# Stepper-driver.net
KiCad netlist of a schematic drawn in Altium Designer
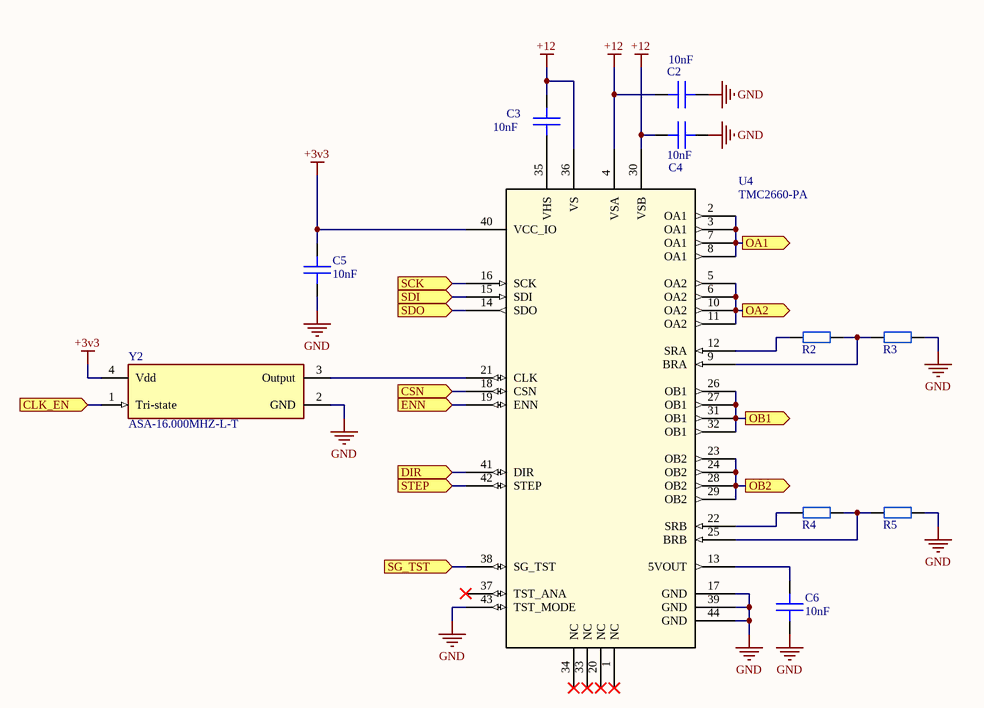
[diagram p0: Stepper-driver.SchDoc]

(export (version "E")
  (design (tool "Eeschema 10.0.6"))
  (components
    (comp (ref "C2")
      (value "10nF")
      (footprint "C0603 (1608)")
      (fields (field (name "Comment") "Cap SMD"))
      (libsource (lib "Moto Symbol Lib") (part "Cap SMD"))
    )
    (comp (ref "C3")
      (value "10nF")
      (footprint "C0603 (1608)")
      (fields (field (name "Comment") "Cap SMD"))
      (libsource (lib "Moto Symbol Lib") (part "Cap SMD"))
    )
    (comp (ref "C4")
      (value "10nF")
      (footprint "C0603 (1608)")
      (fields (field (name "Comment") "Cap SMD"))
      (libsource (lib "Moto Symbol Lib") (part "Cap SMD"))
    )
    (comp (ref "C5")
      (value "10nF")
      (footprint "C0603 (1608)")
      (fields (field (name "Comment") "Cap SMD"))
      (libsource (lib "Moto Symbol Lib") (part "Cap SMD"))
    )
    (comp (ref "C6")
      (value "10nF")
      (footprint "C0603 (1608)")
      (fields (field (name "Comment") "Cap SMD"))
      (libsource (lib "Moto Symbol Lib") (part "Cap SMD"))
    )
    (comp (ref "R2")
      (value "Res")
      (footprint "R0603 (1608)")
      (libsource (lib "Moto Symbol Lib") (part "Resistor EU"))
    )
    (comp (ref "R3")
      (value "Res")
      (footprint "R0603 (1608)")
      (libsource (lib "Moto Symbol Lib") (part "Resistor EU"))
    )
    (comp (ref "R4")
      (value "Res")
      (footprint "R0603 (1608)")
      (libsource (lib "Moto Symbol Lib") (part "Resistor EU"))
    )
    (comp (ref "R5")
      (value "Res")
      (footprint "R0603 (1608)")
      (libsource (lib "Moto Symbol Lib") (part "Resistor EU"))
    )
    (comp (ref "U4")
      (value "TMC2660-PA")
      (footprint "LQFP44_12X12_TRI-M")
      (description "No Description Available")
      (fields (field (name "COPYRIGHT") "Copyright (C) 2016 Accelerated Designs. All rights reserved"))
      (libsource (lib "Moto Symbol Lib") (part "TMC2660-PA"))
    )
    (comp (ref "Y2")
      (value "ASA-16.000MHZ-L-T")
      (footprint "FP-ASA-MFG")
      (description "XTAL OSC XO 16.0000MHZ HCMOS SMD")
      (fields
        (field (name "OCTOPART") "https://octopart.com/asa-16.000mhz-l-t-abracon-21707822")
        (field (name "MANUFACTURER") "Abracon")
      )
      (libsource (lib "Altium Content Vault") (part "7c953fa1d91b086b7cda9813af2bec8"))
    )
  )
  (nets
    (net (code "1") (name "+3v3") (class "Default")
      (node (ref "C5") (pin "2") (pinfunction "2_2") (pintype "power_in"))
      (node (ref "U4") (pin "40") (pinfunction "VCC_IO_40") (pintype "power_in"))
      (node (ref "Y2") (pin "4") (pinfunction "Vdd_4") (pintype "power_in"))
    )
    (net (code "2") (name "+12") (class "Default")
      (node (ref "C2") (pin "2") (pinfunction "2_2") (pintype "power_in"))
      (node (ref "C3") (pin "1") (pinfunction "1_1") (pintype "power_in"))
      (node (ref "C4") (pin "2") (pinfunction "2_2") (pintype "power_in"))
      (node (ref "U4") (pin "30") (pinfunction "VSB_30") (pintype "power_in"))
      (node (ref "U4") (pin "36") (pinfunction "VS_36") (pintype "power_in"))
      (node (ref "U4") (pin "4") (pinfunction "VSA_4") (pintype "power_in"))
    )
    (net (code "3") (name "/CLK_EN") (class "Default")
      (node (ref "Y2") (pin "1") (pinfunction "Tri-state_1") (pintype "input"))
    )
    (net (code "4") (name "/CSN") (class "Default")
      (node (ref "U4") (pin "18") (pinfunction "CSN_18") (pintype "bidirectional"))
    )
    (net (code "5") (name "/DIR") (class "Default")
      (node (ref "U4") (pin "41") (pinfunction "DIR_41") (pintype "bidirectional"))
    )
    (net (code "6") (name "/ENN") (class "Default")
      (node (ref "U4") (pin "19") (pinfunction "ENN_19") (pintype "bidirectional"))
    )
    (net (code "7") (name "/OA1") (class "Default")
      (node (ref "U4") (pin "2") (pinfunction "OA1_2") (pintype "output"))
      (node (ref "U4") (pin "3") (pinfunction "OA1_3") (pintype "output"))
      (node (ref "U4") (pin "7") (pinfunction "OA1_7") (pintype "output"))
      (node (ref "U4") (pin "8") (pinfunction "OA1_8") (pintype "output"))
    )
    (net (code "8") (name "/OA2") (class "Default")
      (node (ref "U4") (pin "10") (pinfunction "OA2_10") (pintype "output"))
      (node (ref "U4") (pin "11") (pinfunction "OA2_11") (pintype "output"))
      (node (ref "U4") (pin "5") (pinfunction "OA2_5") (pintype "output"))
      (node (ref "U4") (pin "6") (pinfunction "OA2_6") (pintype "output"))
    )
    (net (code "9") (name "/OB1") (class "Default")
      (node (ref "U4") (pin "26") (pinfunction "OB1_26") (pintype "output"))
      (node (ref "U4") (pin "27") (pinfunction "OB1_27") (pintype "output"))
      (node (ref "U4") (pin "31") (pinfunction "OB1_31") (pintype "output"))
      (node (ref "U4") (pin "32") (pinfunction "OB1_32") (pintype "output"))
    )
    (net (code "10") (name "/OB2") (class "Default")
      (node (ref "U4") (pin "23") (pinfunction "OB2_23") (pintype "output"))
      (node (ref "U4") (pin "24") (pinfunction "OB2_24") (pintype "output"))
      (node (ref "U4") (pin "28") (pinfunction "OB2_28") (pintype "output"))
      (node (ref "U4") (pin "29") (pinfunction "OB2_29") (pintype "output"))
    )
    (net (code "11") (name "/SCK") (class "Default")
      (node (ref "U4") (pin "16") (pinfunction "SCK_16") (pintype "input"))
    )
    (net (code "12") (name "/SDI") (class "Default")
      (node (ref "U4") (pin "15") (pinfunction "SDI_15") (pintype "input"))
    )
    (net (code "13") (name "/SDO") (class "Default")
      (node (ref "U4") (pin "14") (pinfunction "SDO_14") (pintype "output"))
    )
    (net (code "14") (name "/SG_TST") (class "Default")
      (node (ref "U4") (pin "38") (pinfunction "SG_TST_38") (pintype "bidirectional"))
    )
    (net (code "15") (name "/STEP") (class "Default")
      (node (ref "U4") (pin "42") (pinfunction "STEP_42") (pintype "bidirectional"))
    )
    (net (code "16") (name "GND") (class "Default")
      (node (ref "C2") (pin "1") (pinfunction "1_1") (pintype "power_in"))
      (node (ref "C4") (pin "1") (pinfunction "1_1") (pintype "power_in"))
      (node (ref "C5") (pin "1") (pinfunction "1_1") (pintype "power_in"))
      (node (ref "C6") (pin "1") (pinfunction "1_1") (pintype "power_in"))
      (node (ref "R3") (pin "2") (pinfunction "2_2") (pintype "power_in"))
      (node (ref "R5") (pin "2") (pinfunction "2_2") (pintype "power_in"))
      (node (ref "U4") (pin "17") (pinfunction "GND_17") (pintype "power_in"))
      (node (ref "U4") (pin "39") (pinfunction "GND_39") (pintype "power_in"))
      (node (ref "U4") (pin "43") (pinfunction "TST_MODE_43") (pintype "bidirectional"))
      (node (ref "U4") (pin "44") (pinfunction "GND_44") (pintype "power_in"))
      (node (ref "Y2") (pin "2") (pinfunction "GND_2") (pintype "power_in"))
    )
    (net (code "17") (name "Net-(U4-5VOUT)") (class "Default")
      (node (ref "C6") (pin "2") (pinfunction "2_2") (pintype "power_in"))
      (node (ref "U4") (pin "13") (pinfunction "5VOUT_13") (pintype "output"))
    )
    (net (code "18") (name "Net-(U4-BRA)") (class "Default")
      (node (ref "R2") (pin "2") (pinfunction "2_2") (pintype "power_in"))
      (node (ref "R3") (pin "1") (pinfunction "1_1") (pintype "power_in"))
      (node (ref "U4") (pin "9") (pinfunction "BRA_9") (pintype "input"))
    )
    (net (code "19") (name "Net-(U4-BRB)") (class "Default")
      (node (ref "R4") (pin "2") (pinfunction "2_2") (pintype "power_in"))
      (node (ref "R5") (pin "1") (pinfunction "1_1") (pintype "power_in"))
      (node (ref "U4") (pin "25") (pinfunction "BRB_25") (pintype "input"))
    )
    (net (code "20") (name "Net-(U4-CLK)") (class "Default")
      (node (ref "U4") (pin "21") (pinfunction "CLK_21") (pintype "bidirectional"))
      (node (ref "Y2") (pin "3") (pinfunction "Output_3") (pintype "passive"))
    )
    (net (code "21") (name "Net-(U4-SRA)") (class "Default")
      (node (ref "R2") (pin "1") (pinfunction "1_1") (pintype "power_in"))
      (node (ref "U4") (pin "12") (pinfunction "SRA_12") (pintype "input"))
    )
    (net (code "22") (name "Net-(U4-SRB)") (class "Default")
      (node (ref "R4") (pin "1") (pinfunction "1_1") (pintype "power_in"))
      (node (ref "U4") (pin "22") (pinfunction "SRB_22") (pintype "input"))
    )
    (net (code "23") (name "Net-(U4-VHS)") (class "Default")
      (node (ref "C3") (pin "2") (pinfunction "2_2") (pintype "power_in"))
      (node (ref "U4") (pin "35") (pinfunction "VHS_35") (pintype "power_in"))
    )
    (net (code "24") (name "unconnected-(U4-NC-Pad1)") (class "Default")
      (node (ref "U4") (pin "1") (pinfunction "NC_1") (pintype "passive+no_connect"))
    )
    (net (code "25") (name "unconnected-(U4-NC-Pad20)") (class "Default")
      (node (ref "U4") (pin "20") (pinfunction "NC_20") (pintype "passive+no_connect"))
    )
    (net (code "26") (name "unconnected-(U4-NC-Pad33)") (class "Default")
      (node (ref "U4") (pin "33") (pinfunction "NC_33") (pintype "passive+no_connect"))
    )
    (net (code "27") (name "unconnected-(U4-NC-Pad34)") (class "Default")
      (node (ref "U4") (pin "34") (pinfunction "NC_34") (pintype "passive+no_connect"))
    )
    (net (code "28") (name "unconnected-(U4-TST_ANA-Pad37)") (class "Default")
      (node (ref "U4") (pin "37") (pinfunction "TST_ANA_37") (pintype "bidirectional+no_connect"))
    )
  )
)
